# utilidong-ftdi-uart-lipo-charger-mk-2_0.net
KiCad netlist of a schematic drawn in EAGLE
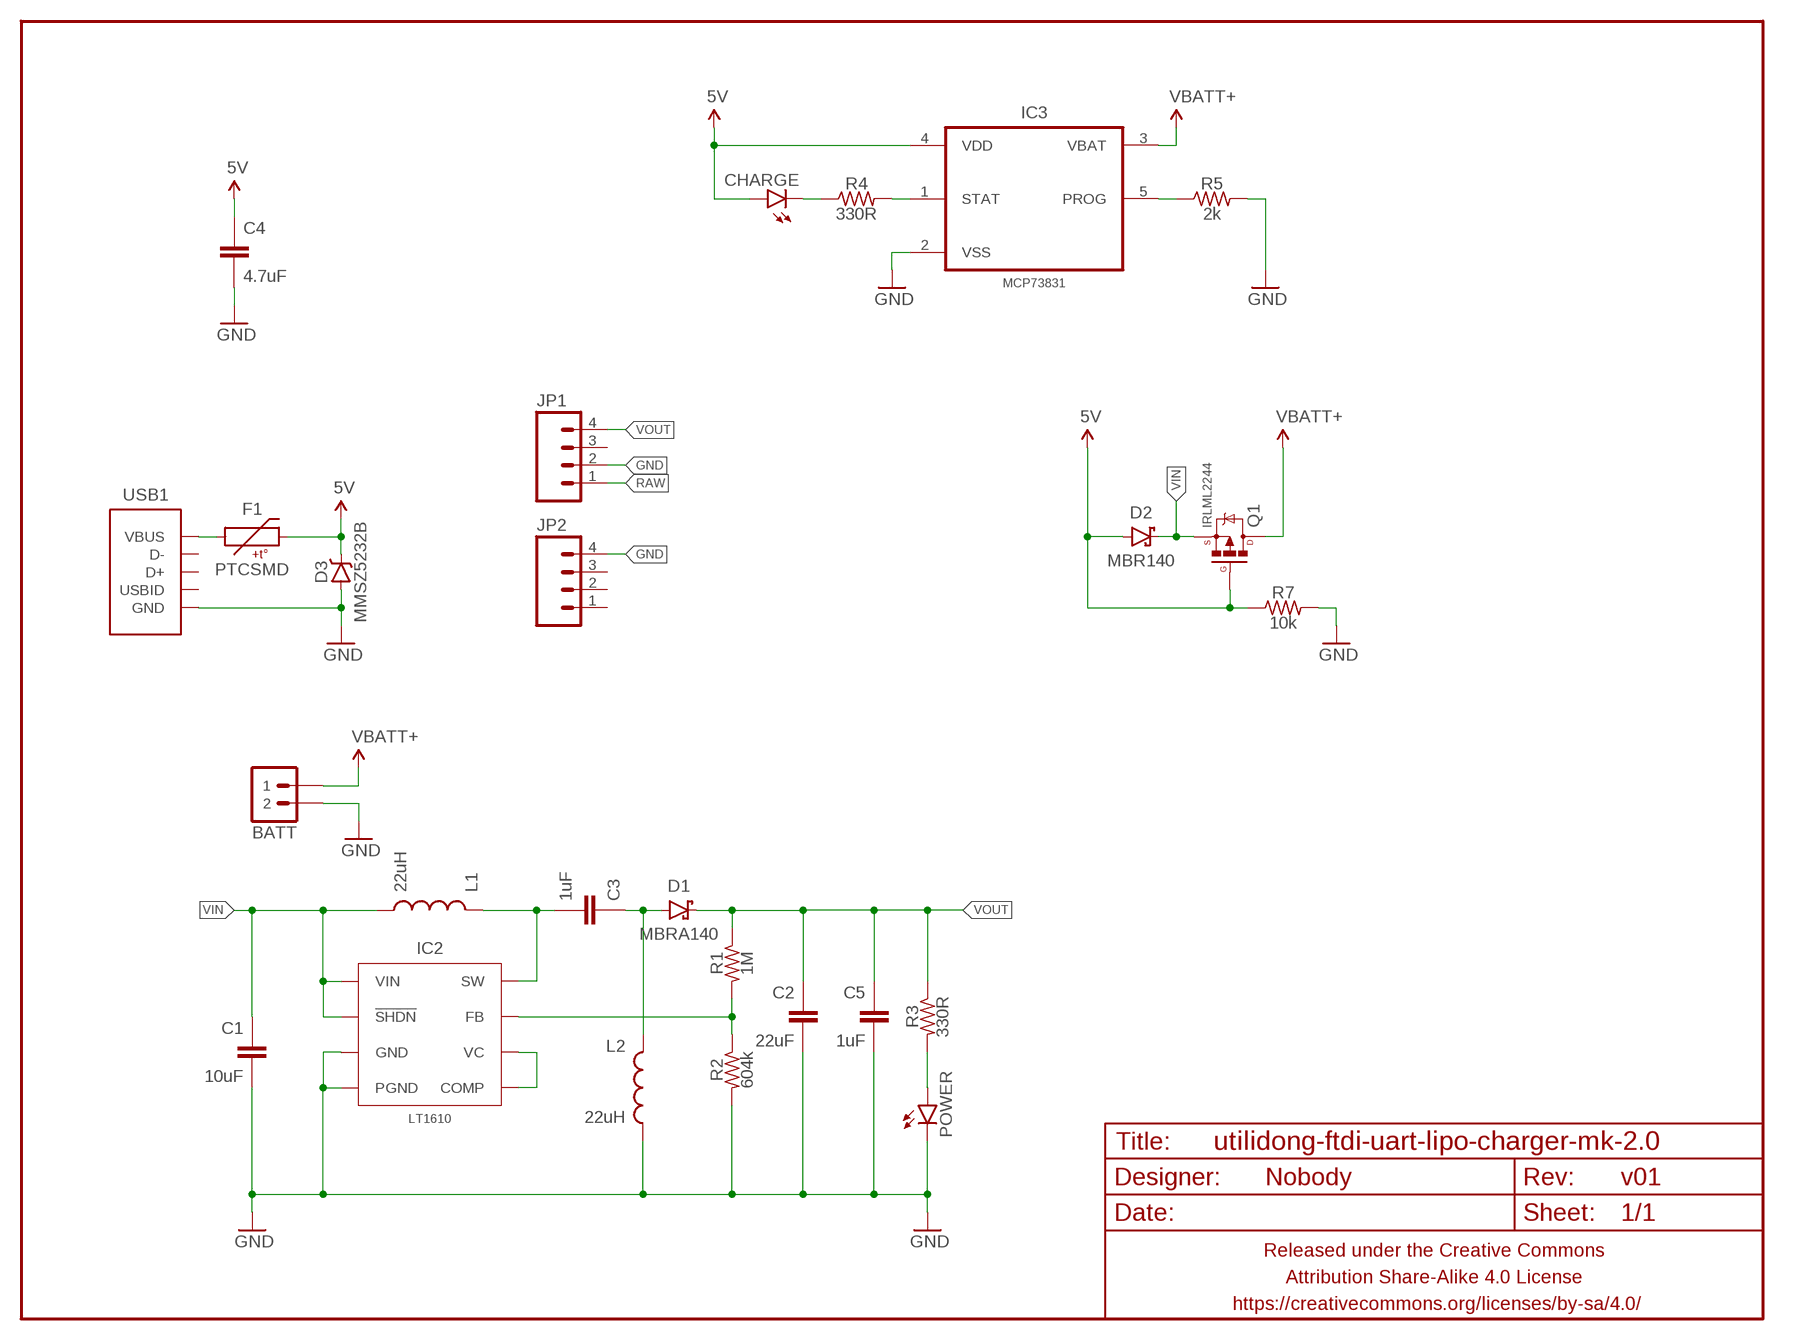
[diagram p0: schematic, sheet 1]

(export (version "E")
  (design (tool "Eeschema 10.0.6"))
  (components
    (comp (ref "BATT")
      (value "M02JST-2MM-SMT")
      (footprint "eagle-import:JST-2-SMD")
      (libsource (lib "eagle-import") (part "M02JST-2MM-SMT"))
    )
    (comp (ref "C1")
      (value "10uF")
      (footprint "eagle-import:C0805")
      (libsource (lib "eagle-import") (part "CAPACITOR-CERAMICC0805"))
    )
    (comp (ref "C2")
      (value "22uF")
      (footprint "eagle-import:C1206")
      (libsource (lib "eagle-import") (part "CAPACITOR-CERAMICC1206"))
    )
    (comp (ref "C3")
      (value "1uF")
      (footprint "eagle-import:C0805")
      (libsource (lib "eagle-import") (part "CAPACITOR-CERAMICC0805"))
    )
    (comp (ref "C4")
      (value "4.7uF")
      (footprint "eagle-import:C0603")
      (libsource (lib "eagle-import") (part "CAPACITOR-CERAMICC0603"))
    )
    (comp (ref "C5")
      (value "1uF")
      (footprint "eagle-import:C0805")
      (libsource (lib "eagle-import") (part "CAPACITOR-CERAMICC0805"))
    )
    (comp (ref "CHARGE")
      (value "LED1206")
      (footprint "eagle-import:LED-1206")
      (libsource (lib "eagle-import") (part "LED1206"))
    )
    (comp (ref "D1")
      (value "MBRA140")
      (footprint "eagle-import:SOD123-SCHOTTKY")
      (libsource (lib "eagle-import") (part "DIODE-SCHOTTKYSOD123"))
    )
    (comp (ref "D2")
      (value "MBR140")
      (footprint "eagle-import:SOD123-SCHOTTKY")
      (libsource (lib "eagle-import") (part "DIODE-SCHOTTKYSOD123"))
    )
    (comp (ref "D3")
      (value "MMSZ5232B")
      (footprint "eagle-import:SOD123-ZENER")
      (libsource (lib "eagle-import") (part "DIODE-ZENERSOD123"))
    )
    (comp (ref "F1")
      (value "PTCSMD")
      (footprint "eagle-import:PTC-1206")
      (libsource (lib "eagle-import") (part "PTCSMD"))
    )
    (comp (ref "FRAME1")
      (value "FRAME-LETTERNO_PACKAGE")
      (footprint "eagle-import:DUMMY")
      (fields (field (name "DESIGNER") "Nobody"))
      (libsource (lib "eagle-import") (part "FRAME-LETTERNO_PACKAGE"))
    )
    (comp (ref "IC2")
      (value "LT1610")
      (footprint "eagle-import:SO08")
      (libsource (lib "eagle-import") (part "LT1610SOICN8"))
    )
    (comp (ref "IC3")
      (value "MCP73831")
      (footprint "eagle-import:SOT95P280X145-5N")
      (fields (field (name "MPN") "MCP73831T-2ACI/OT"))
      (libsource (lib "eagle-import") (part "MCP73831T-2ACI/OT"))
    )
    (comp (ref "JP1")
      (value "M04PTH")
      (footprint "eagle-import:1X04-PTH-VERT")
      (libsource (lib "eagle-import") (part "M04PTH"))
    )
    (comp (ref "JP2")
      (value "M04PTH")
      (footprint "eagle-import:1X04-PTH-VERT")
      (libsource (lib "eagle-import") (part "M04PTH"))
    )
    (comp (ref "L1")
      (value "22uH")
      (footprint "eagle-import:TAIYO-YUDEN-40XX")
      (libsource (lib "eagle-import") (part "INDUCTORTAIYO-YUDEN-40XX"))
    )
    (comp (ref "L2")
      (value "22uH")
      (footprint "eagle-import:TAIYO-YUDEN-40XX")
      (libsource (lib "eagle-import") (part "INDUCTORTAIYO-YUDEN-40XX"))
    )
    (comp (ref "POWER")
      (value "LED1206")
      (footprint "eagle-import:LED-1206")
      (libsource (lib "eagle-import") (part "LED1206"))
    )
    (comp (ref "Q1")
      (value "IRLML2244")
      (footprint "eagle-import:SOT23-3")
      (libsource (lib "eagle-import") (part "MOSFET-PCHANNELIRLML2244"))
    )
    (comp (ref "R1")
      (value "1M")
      (footprint "eagle-import:R0603")
      (libsource (lib "eagle-import") (part "RESISTORR0603"))
    )
    (comp (ref "R2")
      (value "604k")
      (footprint "eagle-import:R0603")
      (libsource (lib "eagle-import") (part "RESISTORR0603"))
    )
    (comp (ref "R3")
      (value "330R")
      (footprint "eagle-import:R0603")
      (libsource (lib "eagle-import") (part "RESISTORR0603"))
    )
    (comp (ref "R4")
      (value "330R")
      (footprint "eagle-import:R0603")
      (libsource (lib "eagle-import") (part "RESISTORR0603"))
    )
    (comp (ref "R5")
      (value "2k")
      (footprint "eagle-import:R0603")
      (libsource (lib "eagle-import") (part "RESISTORR0603"))
    )
    (comp (ref "R7")
      (value "10k")
      (footprint "eagle-import:R0603")
      (libsource (lib "eagle-import") (part "RESISTORR0603"))
    )
    (comp (ref "USB1")
      (value "USB-ABCOMBO")
      (footprint "eagle-import:USB-MICRO-B-FCI-CUTOUT")
      (libsource (lib "eagle-import") (part "USB-ABCOMBO"))
    )
  )
  (nets
    (net (code "1") (name "5V") (class "Default")
      (node (ref "C4") (pin "1") (pinfunction "1_1") (pintype "passive"))
      (node (ref "CHARGE") (pin "A") (pinfunction "A_A") (pintype "passive"))
      (node (ref "D2") (pin "A") (pinfunction "A_A") (pintype "passive"))
      (node (ref "D3") (pin "C") (pinfunction "C_C") (pintype "passive"))
      (node (ref "F1") (pin "2") (pinfunction "2_2") (pintype "passive"))
      (node (ref "IC3") (pin "4") (pinfunction "VDD_4") (pintype "power_in"))
      (node (ref "Q1") (pin "1") (pinfunction "G_1") (pintype "passive"))
      (node (ref "R7") (pin "1") (pinfunction "1_1") (pintype "passive"))
    )
    (net (code "2") (name "GND") (class "Default")
      (node (ref "BATT") (pin "1") (pinfunction "2_1") (pintype "passive"))
      (node (ref "C1") (pin "2") (pinfunction "2_2") (pintype "passive"))
      (node (ref "C2") (pin "2") (pinfunction "2_2") (pintype "passive"))
      (node (ref "C4") (pin "2") (pinfunction "2_2") (pintype "passive"))
      (node (ref "C5") (pin "2") (pinfunction "2_2") (pintype "passive"))
      (node (ref "D3") (pin "A") (pinfunction "A_A") (pintype "passive"))
      (node (ref "IC2") (pin "4") (pinfunction "PGND_4") (pintype "passive"))
      (node (ref "IC2") (pin "7") (pinfunction "GND_7") (pintype "passive"))
      (node (ref "IC3") (pin "2") (pinfunction "VSS_2") (pintype "power_in"))
      (node (ref "JP1") (pin "2") (pinfunction "2_2") (pintype "passive"))
      (node (ref "JP2") (pin "4") (pinfunction "4_4") (pintype "passive"))
      (node (ref "L2") (pin "2") (pinfunction "2_2") (pintype "passive"))
      (node (ref "POWER") (pin "C") (pinfunction "C_C") (pintype "passive"))
      (node (ref "R2") (pin "2") (pinfunction "2_2") (pintype "passive"))
      (node (ref "R5") (pin "2") (pinfunction "2_2") (pintype "passive"))
      (node (ref "R7") (pin "2") (pinfunction "2_2") (pintype "passive"))
      (node (ref "USB1") (pin "5") (pinfunction "GND_5") (pintype "bidirectional"))
      (node (ref "USB1") (pin "P$1") (pinfunction "GND_P$1") (pintype "bidirectional"))
      (node (ref "USB1") (pin "P$2") (pinfunction "GND_P$2") (pintype "bidirectional"))
    )
    (net (code "3") (name "Net-(C3-Pad1)") (class "Default")
      (node (ref "C3") (pin "1") (pinfunction "1_1") (pintype "passive"))
      (node (ref "D1") (pin "A") (pinfunction "A_A") (pintype "passive"))
      (node (ref "L2") (pin "1") (pinfunction "1_1") (pintype "passive"))
    )
    (net (code "4") (name "Net-(CHARGE-PadC)") (class "Default")
      (node (ref "CHARGE") (pin "C") (pinfunction "C_C") (pintype "passive"))
      (node (ref "R4") (pin "1") (pinfunction "1_1") (pintype "passive"))
    )
    (net (code "5") (name "Net-(IC2-COMP)") (class "Default")
      (node (ref "IC2") (pin "1") (pinfunction "VC_1") (pintype "passive"))
      (node (ref "IC2") (pin "8") (pinfunction "COMP_8") (pintype "passive"))
    )
    (net (code "6") (name "Net-(IC2-FB)") (class "Default")
      (node (ref "IC2") (pin "2") (pinfunction "FB_2") (pintype "passive"))
      (node (ref "R1") (pin "2") (pinfunction "2_2") (pintype "passive"))
      (node (ref "R2") (pin "1") (pinfunction "1_1") (pintype "passive"))
    )
    (net (code "7") (name "Net-(IC2-SW)") (class "Default")
      (node (ref "C3") (pin "2") (pinfunction "2_2") (pintype "passive"))
      (node (ref "IC2") (pin "5") (pinfunction "SW_5") (pintype "passive"))
      (node (ref "L1") (pin "1") (pinfunction "1_1") (pintype "passive"))
    )
    (net (code "8") (name "Net-(IC3-PROG)") (class "Default")
      (node (ref "IC3") (pin "5") (pinfunction "PROG_5") (pintype "input"))
      (node (ref "R5") (pin "1") (pinfunction "1_1") (pintype "passive"))
    )
    (net (code "9") (name "Net-(IC3-STAT)") (class "Default")
      (node (ref "IC3") (pin "1") (pinfunction "STAT_1") (pintype "output"))
      (node (ref "R4") (pin "2") (pinfunction "2_2") (pintype "passive"))
    )
    (net (code "10") (name "Net-(POWER-PadA)") (class "Default")
      (node (ref "POWER") (pin "A") (pinfunction "A_A") (pintype "passive"))
      (node (ref "R3") (pin "2") (pinfunction "2_2") (pintype "passive"))
    )
    (net (code "11") (name "Net-(USB1-VBUS)") (class "Default")
      (node (ref "F1") (pin "1") (pinfunction "1_1") (pintype "passive"))
      (node (ref "USB1") (pin "1") (pinfunction "VBUS_1") (pintype "bidirectional"))
    )
    (net (code "12") (name "RAW") (class "Default")
      (node (ref "JP1") (pin "1") (pinfunction "1_1") (pintype "passive"))
    )
    (net (code "13") (name "VBATT+") (class "Default")
      (node (ref "BATT") (pin "2") (pinfunction "1_2") (pintype "passive"))
      (node (ref "IC3") (pin "3") (pinfunction "VBAT_3") (pintype "output"))
      (node (ref "Q1") (pin "3") (pinfunction "D_3") (pintype "passive"))
    )
    (net (code "14") (name "VIN") (class "Default")
      (node (ref "C1") (pin "1") (pinfunction "1_1") (pintype "passive"))
      (node (ref "D2") (pin "C") (pinfunction "C_C") (pintype "passive"))
      (node (ref "IC2") (pin "3") (pinfunction "~{SHDN}_3") (pintype "passive"))
      (node (ref "IC2") (pin "6") (pinfunction "VIN_6") (pintype "passive"))
      (node (ref "L1") (pin "2") (pinfunction "2_2") (pintype "passive"))
      (node (ref "Q1") (pin "2") (pinfunction "S_2") (pintype "passive"))
    )
    (net (code "15") (name "VOUT") (class "Default")
      (node (ref "C2") (pin "1") (pinfunction "1_1") (pintype "passive"))
      (node (ref "C5") (pin "1") (pinfunction "1_1") (pintype "passive"))
      (node (ref "D1") (pin "C") (pinfunction "C_C") (pintype "passive"))
      (node (ref "JP1") (pin "4") (pinfunction "4_4") (pintype "passive"))
      (node (ref "R1") (pin "1") (pinfunction "1_1") (pintype "passive"))
      (node (ref "R3") (pin "1") (pinfunction "1_1") (pintype "passive"))
    )
    (net (code "16") (name "unconnected-(JP1-Pad3)") (class "Default")
      (node (ref "JP1") (pin "3") (pinfunction "3_3") (pintype "passive"))
    )
    (net (code "17") (name "unconnected-(JP2-Pad1)") (class "Default")
      (node (ref "JP2") (pin "1") (pinfunction "1_1") (pintype "passive"))
    )
    (net (code "18") (name "unconnected-(JP2-Pad2)") (class "Default")
      (node (ref "JP2") (pin "2") (pinfunction "2_2") (pintype "passive"))
    )
    (net (code "19") (name "unconnected-(JP2-Pad3)") (class "Default")
      (node (ref "JP2") (pin "3") (pinfunction "3_3") (pintype "passive"))
    )
    (net (code "20") (name "unconnected-(USB1-D+-Pad3)") (class "Default")
      (node (ref "USB1") (pin "3") (pinfunction "D+_3") (pintype "bidirectional"))
    )
    (net (code "21") (name "unconnected-(USB1-D--Pad2)") (class "Default")
      (node (ref "USB1") (pin "2") (pinfunction "D-_2") (pintype "bidirectional"))
    )
    (net (code "22") (name "unconnected-(USB1-USBID-Pad4)") (class "Default")
      (node (ref "USB1") (pin "4") (pinfunction "USBID_4") (pintype "bidirectional"))
    )
  )
)
